# snc98_3x4_Switch-block.net
KiCad netlist of a schematic drawn in EAGLE
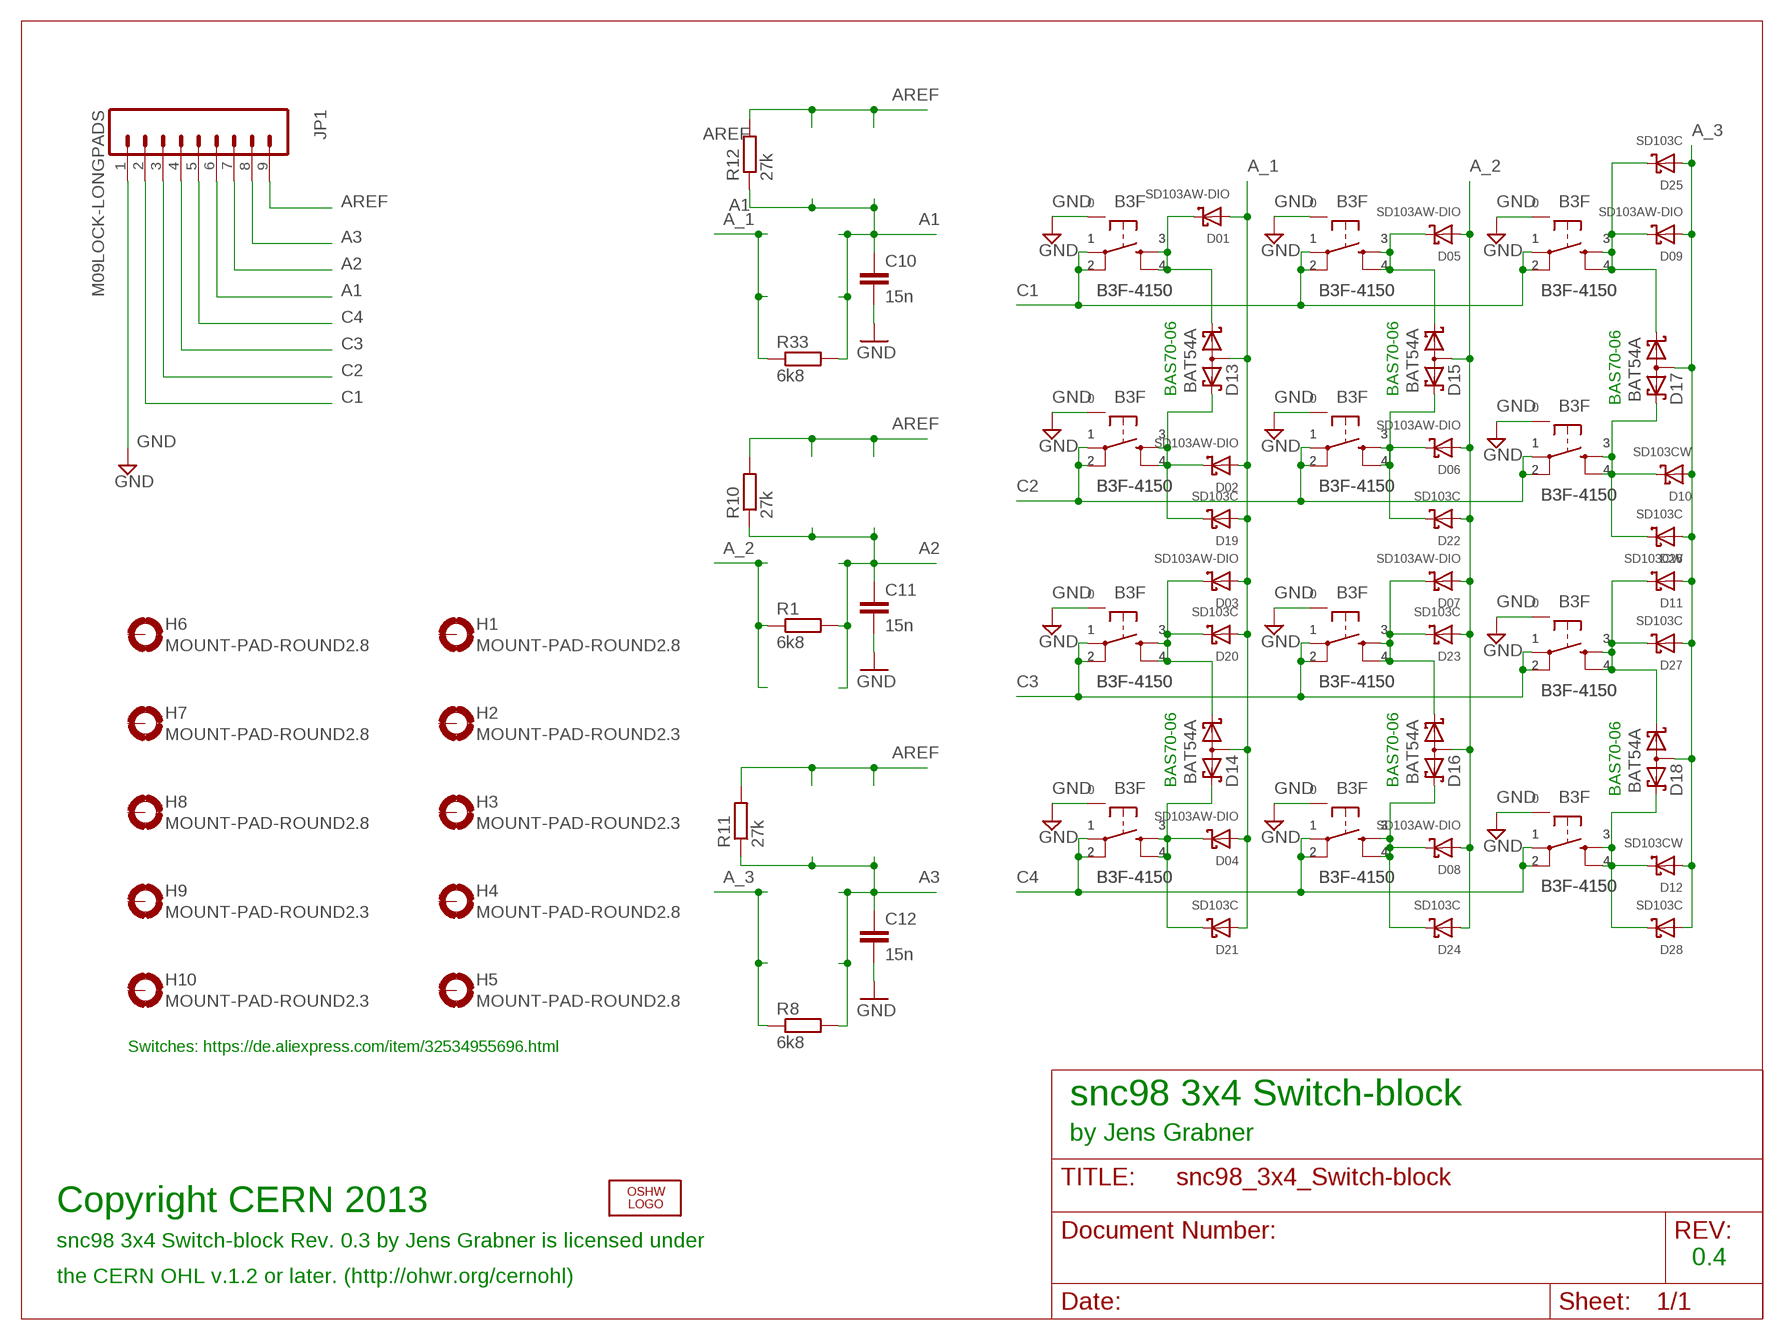
[diagram p0: schematic, sheet 1]

(export (version "E")
  (design (tool "Eeschema 10.0.6"))
  (components
    (comp (ref "C10")
      (value "15n")
      (footprint "eagle-import:C1206K")
      (libsource (lib "eagle-import") (part "C-EUC1206K"))
    )
    (comp (ref "C11")
      (value "15n")
      (footprint "eagle-import:C1206K")
      (libsource (lib "eagle-import") (part "C-EUC1206K"))
    )
    (comp (ref "C12")
      (value "15n")
      (footprint "eagle-import:C1206K")
      (libsource (lib "eagle-import") (part "C-EUC1206K"))
    )
    (comp (ref "D01")
      (value "SD103AW-DIO")
      (footprint "eagle-import:SOD-123F")
      (fields (field (name "MF") "MULTICOMP") (field (name "MPN") "SD103CW-7-F"))
      (libsource (lib "eagle-import") (part "DIODESOD-123F"))
    )
    (comp (ref "D02")
      (value "SD103AW-DIO")
      (footprint "eagle-import:SOD-123F")
      (fields (field (name "MF") "MULTICOMP") (field (name "MPN") "SD103CW-7-F"))
      (libsource (lib "eagle-import") (part "DIODESOD-123F"))
    )
    (comp (ref "D03")
      (value "SD103AW-DIO")
      (footprint "eagle-import:SOD-123F")
      (fields (field (name "MF") "MULTICOMP") (field (name "MPN") "SD103CW-7-F"))
      (libsource (lib "eagle-import") (part "DIODESOD-123F"))
    )
    (comp (ref "D04")
      (value "SD103AW-DIO")
      (footprint "eagle-import:SOD-123F")
      (fields (field (name "MF") "MULTICOMP") (field (name "MPN") "SD103CW-7-F"))
      (libsource (lib "eagle-import") (part "DIODESOD-123F"))
    )
    (comp (ref "D05")
      (value "SD103AW-DIO")
      (footprint "eagle-import:SOD-123F")
      (fields (field (name "MF") "MULTICOMP") (field (name "MPN") "SD103CW-7-F"))
      (libsource (lib "eagle-import") (part "DIODESOD-123F"))
    )
    (comp (ref "D06")
      (value "SD103AW-DIO")
      (footprint "eagle-import:SOD-123F")
      (fields (field (name "MF") "MULTICOMP") (field (name "MPN") "SD103CW-7-F"))
      (libsource (lib "eagle-import") (part "DIODESOD-123F"))
    )
    (comp (ref "D07")
      (value "SD103AW-DIO")
      (footprint "eagle-import:SOD-123F")
      (fields (field (name "MF") "MULTICOMP") (field (name "MPN") "SD103CW-7-F"))
      (libsource (lib "eagle-import") (part "DIODESOD-123F"))
    )
    (comp (ref "D08")
      (value "SD103AW-DIO")
      (footprint "eagle-import:SOD-123F")
      (fields (field (name "MF") "MULTICOMP") (field (name "MPN") "SD103CW-7-F"))
      (libsource (lib "eagle-import") (part "DIODESOD-123F"))
    )
    (comp (ref "D09")
      (value "SD103AW-DIO")
      (footprint "eagle-import:SOD-123F")
      (fields (field (name "MF") "MULTICOMP") (field (name "MPN") "SD103CW-7-F"))
      (libsource (lib "eagle-import") (part "DIODESOD-123F"))
    )
    (comp (ref "D10")
      (value "SD103CW")
      (footprint "eagle-import:SOD-123F")
      (fields (field (name "MF") "MULTICOMP") (field (name "MPN") "SD103CW-7-F"))
      (libsource (lib "eagle-import") (part "DIODESOD-123F"))
    )
    (comp (ref "D11")
      (value "SD103CW")
      (footprint "eagle-import:SOD-123F")
      (fields (field (name "MF") "MULTICOMP") (field (name "MPN") "SD103CW-7-F"))
      (libsource (lib "eagle-import") (part "DIODESOD-123F"))
    )
    (comp (ref "D12")
      (value "SD103CW")
      (footprint "eagle-import:SOD-123F")
      (fields (field (name "MF") "MULTICOMP") (field (name "MPN") "SD103CW-7-F"))
      (libsource (lib "eagle-import") (part "DIODESOD-123F"))
    )
    (comp (ref "D13")
      (value "BAT54A")
      (footprint "eagle-import:SOT23")
      (libsource (lib "eagle-import") (part "BAT54A"))
    )
    (comp (ref "D14")
      (value "BAT54A")
      (footprint "eagle-import:SOT23")
      (libsource (lib "eagle-import") (part "BAT54A"))
    )
    (comp (ref "D15")
      (value "BAT54A")
      (footprint "eagle-import:SOT23")
      (libsource (lib "eagle-import") (part "BAT54A"))
    )
    (comp (ref "D16")
      (value "BAT54A")
      (footprint "eagle-import:SOT23")
      (libsource (lib "eagle-import") (part "BAT54A"))
    )
    (comp (ref "D17")
      (value "BAT54A")
      (footprint "eagle-import:SOT23")
      (libsource (lib "eagle-import") (part "BAT54A"))
    )
    (comp (ref "D18")
      (value "BAT54A")
      (footprint "eagle-import:SOT23")
      (libsource (lib "eagle-import") (part "BAT54A"))
    )
    (comp (ref "D19")
      (value "SD103C")
      (footprint "eagle-import:280MIL-TH")
      (fields (field (name "MF") "MULTICOMP") (field (name "MPN") "SD103CW-7-F"))
      (libsource (lib "eagle-import") (part "DIODE280MIL-TH"))
    )
    (comp (ref "D20")
      (value "SD103C")
      (footprint "eagle-import:280MIL-TH")
      (fields (field (name "MF") "MULTICOMP") (field (name "MPN") "SD103CW-7-F"))
      (libsource (lib "eagle-import") (part "DIODE280MIL-TH"))
    )
    (comp (ref "D21")
      (value "SD103C")
      (footprint "eagle-import:280MIL-TH")
      (fields (field (name "MF") "MULTICOMP") (field (name "MPN") "SD103CW-7-F"))
      (libsource (lib "eagle-import") (part "DIODE280MIL-TH"))
    )
    (comp (ref "D22")
      (value "SD103C")
      (footprint "eagle-import:280MIL-TH")
      (fields (field (name "MF") "MULTICOMP") (field (name "MPN") "SD103CW-7-F"))
      (libsource (lib "eagle-import") (part "DIODE280MIL-TH"))
    )
    (comp (ref "D23")
      (value "SD103C")
      (footprint "eagle-import:280MIL-TH")
      (fields (field (name "MF") "MULTICOMP") (field (name "MPN") "SD103CW-7-F"))
      (libsource (lib "eagle-import") (part "DIODE280MIL-TH"))
    )
    (comp (ref "D24")
      (value "SD103C")
      (footprint "eagle-import:280MIL-TH")
      (fields (field (name "MF") "MULTICOMP") (field (name "MPN") "SD103CW-7-F"))
      (libsource (lib "eagle-import") (part "DIODE280MIL-TH"))
    )
    (comp (ref "D25")
      (value "SD103C")
      (footprint "eagle-import:280MIL-TH")
      (fields (field (name "MF") "MULTICOMP") (field (name "MPN") "SD103CW-7-F"))
      (libsource (lib "eagle-import") (part "DIODE280MIL-TH"))
    )
    (comp (ref "D26")
      (value "SD103C")
      (footprint "eagle-import:280MIL-TH")
      (fields (field (name "MF") "MULTICOMP") (field (name "MPN") "SD103CW-7-F"))
      (libsource (lib "eagle-import") (part "DIODE280MIL-TH"))
    )
    (comp (ref "D27")
      (value "SD103C")
      (footprint "eagle-import:280MIL-TH")
      (fields (field (name "MF") "MULTICOMP") (field (name "MPN") "SD103CW-7-F"))
      (libsource (lib "eagle-import") (part "DIODE280MIL-TH"))
    )
    (comp (ref "D28")
      (value "SD103C")
      (footprint "eagle-import:280MIL-TH")
      (fields (field (name "MF") "MULTICOMP") (field (name "MPN") "SD103CW-7-F"))
      (libsource (lib "eagle-import") (part "DIODE280MIL-TH"))
    )
    (comp (ref "H1")
      (value "MOUNT-PAD-ROUND2.8")
      (footprint "eagle-import:2,8-PAD")
      (libsource (lib "eagle-import") (part "MOUNT-PAD-ROUND2.8"))
    )
    (comp (ref "H2")
      (value "MOUNT-PAD-ROUND2.3")
      (footprint "eagle-import:2,3-PAD")
      (libsource (lib "eagle-import") (part "MOUNT-PAD-ROUND2.3"))
    )
    (comp (ref "H3")
      (value "MOUNT-PAD-ROUND2.3")
      (footprint "eagle-import:2,3-PAD")
      (libsource (lib "eagle-import") (part "MOUNT-PAD-ROUND2.3"))
    )
    (comp (ref "H4")
      (value "MOUNT-PAD-ROUND2.8")
      (footprint "eagle-import:2,8-PAD")
      (libsource (lib "eagle-import") (part "MOUNT-PAD-ROUND2.8"))
    )
    (comp (ref "H5")
      (value "MOUNT-PAD-ROUND2.8")
      (footprint "eagle-import:2,8-PAD")
      (libsource (lib "eagle-import") (part "MOUNT-PAD-ROUND2.8"))
    )
    (comp (ref "H6")
      (value "MOUNT-PAD-ROUND2.8")
      (footprint "eagle-import:2,8-PAD")
      (libsource (lib "eagle-import") (part "MOUNT-PAD-ROUND2.8"))
    )
    (comp (ref "H7")
      (value "MOUNT-PAD-ROUND2.8")
      (footprint "eagle-import:2,8-PAD")
      (libsource (lib "eagle-import") (part "MOUNT-PAD-ROUND2.8"))
    )
    (comp (ref "H8")
      (value "MOUNT-PAD-ROUND2.8")
      (footprint "eagle-import:2,8-PAD")
      (libsource (lib "eagle-import") (part "MOUNT-PAD-ROUND2.8"))
    )
    (comp (ref "H9")
      (value "MOUNT-PAD-ROUND2.3")
      (footprint "eagle-import:2,3-PAD")
      (libsource (lib "eagle-import") (part "MOUNT-PAD-ROUND2.3"))
    )
    (comp (ref "H10")
      (value "MOUNT-PAD-ROUND2.3")
      (footprint "eagle-import:2,3-PAD")
      (libsource (lib "eagle-import") (part "MOUNT-PAD-ROUND2.3"))
    )
    (comp (ref "JP1")
      (value "M09LOCK-LONGPADS")
      (footprint "eagle-import:1X09_LOCK_LONGPADS")
      (libsource (lib "eagle-import") (part "M09LOCK-LONGPADS"))
    )
    (comp (ref "LOGO1")
      (value "OSHW_LOGO_8MILX0150-NT")
      (footprint "eagle-import:OSHW_8X150_NOTEXT")
      (libsource (lib "eagle-import") (part "OSHW_LOGO_8MILX0150-NT"))
    )
    (comp (ref "R1")
      (value "6k8")
      (footprint "eagle-import:M0805")
      (libsource (lib "eagle-import") (part "R-EU_M0805"))
    )
    (comp (ref "R8")
      (value "6k8")
      (footprint "eagle-import:M0805")
      (libsource (lib "eagle-import") (part "R-EU_M0805"))
    )
    (comp (ref "R10")
      (value "27k")
      (footprint "eagle-import:M0805")
      (libsource (lib "eagle-import") (part "R-EU_M0805"))
    )
    (comp (ref "R11")
      (value "27k")
      (footprint "eagle-import:M0805")
      (libsource (lib "eagle-import") (part "R-EU_M0805"))
    )
    (comp (ref "R12")
      (value "27k")
      (footprint "eagle-import:M0805")
      (libsource (lib "eagle-import") (part "R-EU_M0805"))
    )
    (comp (ref "R33")
      (value "6k8")
      (footprint "eagle-import:M0805")
      (libsource (lib "eagle-import") (part "R-EU_M0805"))
    )
    (comp (ref "S1")
      (value "B3F-4150")
      (footprint "eagle-import:TACTILE-PTH-12MM")
      (libsource (lib "eagle-import") (part "TACTILE_SWITCHTACTILE_SWITCH_PTH-12MM"))
    )
    (comp (ref "S2")
      (value "B3F-4150")
      (footprint "eagle-import:TACTILE-PTH-12MM")
      (libsource (lib "eagle-import") (part "TACTILE_SWITCHTACTILE_SWITCH_PTH-12MM"))
    )
    (comp (ref "S3")
      (value "B3F-4150")
      (footprint "eagle-import:TACTILE-PTH-12MM")
      (libsource (lib "eagle-import") (part "TACTILE_SWITCHTACTILE_SWITCH_PTH-12MM"))
    )
    (comp (ref "S4")
      (value "B3F-4150")
      (footprint "eagle-import:TACTILE-PTH-12MM")
      (libsource (lib "eagle-import") (part "TACTILE_SWITCHTACTILE_SWITCH_PTH-12MM"))
    )
    (comp (ref "S5")
      (value "B3F-4150")
      (footprint "eagle-import:TACTILE-PTH-12MM")
      (libsource (lib "eagle-import") (part "TACTILE_SWITCHTACTILE_SWITCH_PTH-12MM"))
    )
    (comp (ref "S6")
      (value "B3F-4150")
      (footprint "eagle-import:TACTILE-PTH-12MM")
      (libsource (lib "eagle-import") (part "TACTILE_SWITCHTACTILE_SWITCH_PTH-12MM"))
    )
    (comp (ref "S7")
      (value "B3F-4150")
      (footprint "eagle-import:TACTILE-PTH-12MM")
      (libsource (lib "eagle-import") (part "TACTILE_SWITCHTACTILE_SWITCH_PTH-12MM"))
    )
    (comp (ref "S8")
      (value "B3F-4150")
      (footprint "eagle-import:TACTILE-PTH-12MM")
      (libsource (lib "eagle-import") (part "TACTILE_SWITCHTACTILE_SWITCH_PTH-12MM"))
    )
    (comp (ref "S9")
      (value "B3F-4150")
      (footprint "eagle-import:TACTILE-PTH-12MM")
      (libsource (lib "eagle-import") (part "TACTILE_SWITCHTACTILE_SWITCH_PTH-12MM"))
    )
    (comp (ref "S10")
      (value "B3F-4150")
      (footprint "eagle-import:TACTILE-PTH-12MM")
      (libsource (lib "eagle-import") (part "TACTILE_SWITCHTACTILE_SWITCH_PTH-12MM"))
    )
    (comp (ref "S11")
      (value "B3F-4150")
      (footprint "eagle-import:TACTILE-PTH-12MM")
      (libsource (lib "eagle-import") (part "TACTILE_SWITCHTACTILE_SWITCH_PTH-12MM"))
    )
    (comp (ref "S12")
      (value "B3F-4150")
      (footprint "eagle-import:TACTILE-PTH-12MM")
      (libsource (lib "eagle-import") (part "TACTILE_SWITCHTACTILE_SWITCH_PTH-12MM"))
    )
  )
  (nets
    (net (code "1") (name "/A1") (class "Default")
      (node (ref "C10") (pin "1") (pinfunction "1_1") (pintype "passive"))
      (node (ref "JP1") (pin "6") (pinfunction "6_6") (pintype "passive"))
      (node (ref "R12") (pin "1") (pinfunction "1_1") (pintype "passive"))
      (node (ref "R33") (pin "2") (pinfunction "2_2") (pintype "passive"))
    )
    (net (code "2") (name "/A2") (class "Default")
      (node (ref "C11") (pin "1") (pinfunction "1_1") (pintype "passive"))
      (node (ref "JP1") (pin "7") (pinfunction "7_7") (pintype "passive"))
      (node (ref "R1") (pin "2") (pinfunction "2_2") (pintype "passive"))
      (node (ref "R10") (pin "1") (pinfunction "1_1") (pintype "passive"))
    )
    (net (code "3") (name "/A3") (class "Default")
      (node (ref "C12") (pin "1") (pinfunction "1_1") (pintype "passive"))
      (node (ref "JP1") (pin "8") (pinfunction "8_8") (pintype "passive"))
      (node (ref "R11") (pin "1") (pinfunction "1_1") (pintype "passive"))
      (node (ref "R8") (pin "2") (pinfunction "2_2") (pintype "passive"))
    )
    (net (code "4") (name "/AREF") (class "Default")
      (node (ref "JP1") (pin "9") (pinfunction "9_9") (pintype "passive"))
      (node (ref "R10") (pin "2") (pinfunction "2_2") (pintype "passive"))
      (node (ref "R11") (pin "2") (pinfunction "2_2") (pintype "passive"))
      (node (ref "R12") (pin "2") (pinfunction "2_2") (pintype "passive"))
    )
    (net (code "5") (name "/A_1") (class "Default")
      (node (ref "D01") (pin "A") (pinfunction "A_A") (pintype "passive"))
      (node (ref "D02") (pin "A") (pinfunction "A_A") (pintype "passive"))
      (node (ref "D03") (pin "A") (pinfunction "A_A") (pintype "passive"))
      (node (ref "D04") (pin "A") (pinfunction "A_A") (pintype "passive"))
      (node (ref "D13") (pin "3") (pinfunction "AA_3") (pintype "passive"))
      (node (ref "D14") (pin "3") (pinfunction "AA_3") (pintype "passive"))
      (node (ref "D19") (pin "P$1") (pinfunction "A_P$1") (pintype "passive"))
      (node (ref "D20") (pin "P$1") (pinfunction "A_P$1") (pintype "passive"))
      (node (ref "D21") (pin "P$1") (pinfunction "A_P$1") (pintype "passive"))
      (node (ref "R33") (pin "1") (pinfunction "1_1") (pintype "passive"))
    )
    (net (code "6") (name "/A_2") (class "Default")
      (node (ref "D05") (pin "A") (pinfunction "A_A") (pintype "passive"))
      (node (ref "D06") (pin "A") (pinfunction "A_A") (pintype "passive"))
      (node (ref "D07") (pin "A") (pinfunction "A_A") (pintype "passive"))
      (node (ref "D08") (pin "A") (pinfunction "A_A") (pintype "passive"))
      (node (ref "D15") (pin "3") (pinfunction "AA_3") (pintype "passive"))
      (node (ref "D16") (pin "3") (pinfunction "AA_3") (pintype "passive"))
      (node (ref "D22") (pin "P$1") (pinfunction "A_P$1") (pintype "passive"))
      (node (ref "D23") (pin "P$1") (pinfunction "A_P$1") (pintype "passive"))
      (node (ref "D24") (pin "P$1") (pinfunction "A_P$1") (pintype "passive"))
      (node (ref "R1") (pin "1") (pinfunction "1_1") (pintype "passive"))
    )
    (net (code "7") (name "/A_3") (class "Default")
      (node (ref "D09") (pin "A") (pinfunction "A_A") (pintype "passive"))
      (node (ref "D10") (pin "A") (pinfunction "A_A") (pintype "passive"))
      (node (ref "D11") (pin "A") (pinfunction "A_A") (pintype "passive"))
      (node (ref "D12") (pin "A") (pinfunction "A_A") (pintype "passive"))
      (node (ref "D17") (pin "3") (pinfunction "AA_3") (pintype "passive"))
      (node (ref "D18") (pin "3") (pinfunction "AA_3") (pintype "passive"))
      (node (ref "D25") (pin "P$1") (pinfunction "A_P$1") (pintype "passive"))
      (node (ref "D26") (pin "P$1") (pinfunction "A_P$1") (pintype "passive"))
      (node (ref "D27") (pin "P$1") (pinfunction "A_P$1") (pintype "passive"))
      (node (ref "D28") (pin "P$1") (pinfunction "A_P$1") (pintype "passive"))
      (node (ref "R8") (pin "1") (pinfunction "1_1") (pintype "passive"))
    )
    (net (code "8") (name "/C1") (class "Default")
      (node (ref "JP1") (pin "2") (pinfunction "2_2") (pintype "passive"))
      (node (ref "S1") (pin "P$1") (pinfunction "1_P$1") (pintype "passive"))
      (node (ref "S1") (pin "P$11") (pinfunction "1_P$11") (pintype "passive"))
      (node (ref "S1") (pin "P$12") (pinfunction "2_P$12") (pintype "passive"))
      (node (ref "S1") (pin "P$2") (pinfunction "2_P$2") (pintype "passive"))
      (node (ref "S1") (pin "P$21") (pinfunction "1_P$21") (pintype "passive"))
      (node (ref "S1") (pin "P$22") (pinfunction "2_P$22") (pintype "passive"))
      (node (ref "S5") (pin "P$1") (pinfunction "1_P$1") (pintype "passive"))
      (node (ref "S5") (pin "P$11") (pinfunction "1_P$11") (pintype "passive"))
      (node (ref "S5") (pin "P$12") (pinfunction "2_P$12") (pintype "passive"))
      (node (ref "S5") (pin "P$2") (pinfunction "2_P$2") (pintype "passive"))
      (node (ref "S5") (pin "P$21") (pinfunction "1_P$21") (pintype "passive"))
      (node (ref "S5") (pin "P$22") (pinfunction "2_P$22") (pintype "passive"))
      (node (ref "S9") (pin "P$1") (pinfunction "1_P$1") (pintype "passive"))
      (node (ref "S9") (pin "P$11") (pinfunction "1_P$11") (pintype "passive"))
      (node (ref "S9") (pin "P$12") (pinfunction "2_P$12") (pintype "passive"))
      (node (ref "S9") (pin "P$2") (pinfunction "2_P$2") (pintype "passive"))
      (node (ref "S9") (pin "P$21") (pinfunction "1_P$21") (pintype "passive"))
      (node (ref "S9") (pin "P$22") (pinfunction "2_P$22") (pintype "passive"))
    )
    (net (code "9") (name "/C2") (class "Default")
      (node (ref "JP1") (pin "3") (pinfunction "3_3") (pintype "passive"))
      (node (ref "S10") (pin "P$1") (pinfunction "1_P$1") (pintype "passive"))
      (node (ref "S10") (pin "P$11") (pinfunction "1_P$11") (pintype "passive"))
      (node (ref "S10") (pin "P$12") (pinfunction "2_P$12") (pintype "passive"))
      (node (ref "S10") (pin "P$2") (pinfunction "2_P$2") (pintype "passive"))
      (node (ref "S10") (pin "P$21") (pinfunction "1_P$21") (pintype "passive"))
      (node (ref "S10") (pin "P$22") (pinfunction "2_P$22") (pintype "passive"))
      (node (ref "S2") (pin "P$1") (pinfunction "1_P$1") (pintype "passive"))
      (node (ref "S2") (pin "P$11") (pinfunction "1_P$11") (pintype "passive"))
      (node (ref "S2") (pin "P$12") (pinfunction "2_P$12") (pintype "passive"))
      (node (ref "S2") (pin "P$2") (pinfunction "2_P$2") (pintype "passive"))
      (node (ref "S2") (pin "P$21") (pinfunction "1_P$21") (pintype "passive"))
      (node (ref "S2") (pin "P$22") (pinfunction "2_P$22") (pintype "passive"))
      (node (ref "S6") (pin "P$1") (pinfunction "1_P$1") (pintype "passive"))
      (node (ref "S6") (pin "P$11") (pinfunction "1_P$11") (pintype "passive"))
      (node (ref "S6") (pin "P$12") (pinfunction "2_P$12") (pintype "passive"))
      (node (ref "S6") (pin "P$2") (pinfunction "2_P$2") (pintype "passive"))
      (node (ref "S6") (pin "P$21") (pinfunction "1_P$21") (pintype "passive"))
      (node (ref "S6") (pin "P$22") (pinfunction "2_P$22") (pintype "passive"))
    )
    (net (code "10") (name "/C3") (class "Default")
      (node (ref "JP1") (pin "4") (pinfunction "4_4") (pintype "passive"))
      (node (ref "S11") (pin "P$1") (pinfunction "1_P$1") (pintype "passive"))
      (node (ref "S11") (pin "P$11") (pinfunction "1_P$11") (pintype "passive"))
      (node (ref "S11") (pin "P$12") (pinfunction "2_P$12") (pintype "passive"))
      (node (ref "S11") (pin "P$2") (pinfunction "2_P$2") (pintype "passive"))
      (node (ref "S11") (pin "P$21") (pinfunction "1_P$21") (pintype "passive"))
      (node (ref "S11") (pin "P$22") (pinfunction "2_P$22") (pintype "passive"))
      (node (ref "S3") (pin "P$1") (pinfunction "1_P$1") (pintype "passive"))
      (node (ref "S3") (pin "P$11") (pinfunction "1_P$11") (pintype "passive"))
      (node (ref "S3") (pin "P$12") (pinfunction "2_P$12") (pintype "passive"))
      (node (ref "S3") (pin "P$2") (pinfunction "2_P$2") (pintype "passive"))
      (node (ref "S3") (pin "P$21") (pinfunction "1_P$21") (pintype "passive"))
      (node (ref "S3") (pin "P$22") (pinfunction "2_P$22") (pintype "passive"))
      (node (ref "S7") (pin "P$1") (pinfunction "1_P$1") (pintype "passive"))
      (node (ref "S7") (pin "P$11") (pinfunction "1_P$11") (pintype "passive"))
      (node (ref "S7") (pin "P$12") (pinfunction "2_P$12") (pintype "passive"))
      (node (ref "S7") (pin "P$2") (pinfunction "2_P$2") (pintype "passive"))
      (node (ref "S7") (pin "P$21") (pinfunction "1_P$21") (pintype "passive"))
      (node (ref "S7") (pin "P$22") (pinfunction "2_P$22") (pintype "passive"))
    )
    (net (code "11") (name "/C4") (class "Default")
      (node (ref "JP1") (pin "5") (pinfunction "5_5") (pintype "passive"))
      (node (ref "S12") (pin "P$1") (pinfunction "1_P$1") (pintype "passive"))
      (node (ref "S12") (pin "P$11") (pinfunction "1_P$11") (pintype "passive"))
      (node (ref "S12") (pin "P$12") (pinfunction "2_P$12") (pintype "passive"))
      (node (ref "S12") (pin "P$2") (pinfunction "2_P$2") (pintype "passive"))
      (node (ref "S12") (pin "P$21") (pinfunction "1_P$21") (pintype "passive"))
      (node (ref "S12") (pin "P$22") (pinfunction "2_P$22") (pintype "passive"))
      (node (ref "S4") (pin "P$1") (pinfunction "1_P$1") (pintype "passive"))
      (node (ref "S4") (pin "P$11") (pinfunction "1_P$11") (pintype "passive"))
      (node (ref "S4") (pin "P$12") (pinfunction "2_P$12") (pintype "passive"))
      (node (ref "S4") (pin "P$2") (pinfunction "2_P$2") (pintype "passive"))
      (node (ref "S4") (pin "P$21") (pinfunction "1_P$21") (pintype "passive"))
      (node (ref "S4") (pin "P$22") (pinfunction "2_P$22") (pintype "passive"))
      (node (ref "S8") (pin "P$1") (pinfunction "1_P$1") (pintype "passive"))
      (node (ref "S8") (pin "P$11") (pinfunction "1_P$11") (pintype "passive"))
      (node (ref "S8") (pin "P$12") (pinfunction "2_P$12") (pintype "passive"))
      (node (ref "S8") (pin "P$2") (pinfunction "2_P$2") (pintype "passive"))
      (node (ref "S8") (pin "P$21") (pinfunction "1_P$21") (pintype "passive"))
      (node (ref "S8") (pin "P$22") (pinfunction "2_P$22") (pintype "passive"))
    )
    (net (code "12") (name "GND") (class "Default")
      (node (ref "C10") (pin "2") (pinfunction "2_2") (pintype "passive"))
      (node (ref "C11") (pin "2") (pinfunction "2_2") (pintype "passive"))
      (node (ref "C12") (pin "2") (pinfunction "2_2") (pintype "passive"))
      (node (ref "JP1") (pin "1") (pinfunction "1_1") (pintype "passive"))
      (node (ref "S1") (pin "P$15") (pinfunction "5_P$15") (pintype "passive"))
      (node (ref "S10") (pin "P$15") (pinfunction "5_P$15") (pintype "passive"))
      (node (ref "S11") (pin "P$15") (pinfunction "5_P$15") (pintype "passive"))
      (node (ref "S12") (pin "P$15") (pinfunction "5_P$15") (pintype "passive"))
      (node (ref "S2") (pin "P$15") (pinfunction "5_P$15") (pintype "passive"))
      (node (ref "S3") (pin "P$15") (pinfunction "5_P$15") (pintype "passive"))
      (node (ref "S4") (pin "P$15") (pinfunction "5_P$15") (pintype "passive"))
      (node (ref "S5") (pin "P$15") (pinfunction "5_P$15") (pintype "passive"))
      (node (ref "S6") (pin "P$15") (pinfunction "5_P$15") (pintype "passive"))
      (node (ref "S7") (pin "P$15") (pinfunction "5_P$15") (pintype "passive"))
      (node (ref "S8") (pin "P$15") (pinfunction "5_P$15") (pintype "passive"))
      (node (ref "S9") (pin "P$15") (pinfunction "5_P$15") (pintype "passive"))
    )
    (net (code "13") (name "Net-(D13-K1)") (class "Default")
      (node (ref "D01") (pin "C") (pinfunction "C_C") (pintype "passive"))
      (node (ref "D13") (pin "1") (pinfunction "K1_1") (pintype "passive"))
      (node (ref "S1") (pin "P$13") (pinfunction "3_P$13") (pintype "passive"))
      (node (ref "S1") (pin "P$14") (pinfunction "4_P$14") (pintype "passive"))
      (node (ref "S1") (pin "P$23") (pinfunction "3_P$23") (pintype "passive"))
      (node (ref "S1") (pin "P$24") (pinfunction "4_P$24") (pintype "passive"))
      (node (ref "S1") (pin "P$3") (pinfunction "3_P$3") (pintype "passive"))
      (node (ref "S1") (pin "P$4") (pinfunction "4_P$4") (pintype "passive"))
    )
    (net (code "14") (name "Net-(D13-K2)") (class "Default")
      (node (ref "D02") (pin "C") (pinfunction "C_C") (pintype "passive"))
      (node (ref "D13") (pin "2") (pinfunction "K2_2") (pintype "passive"))
      (node (ref "D19") (pin "P$2") (pinfunction "C_P$2") (pintype "passive"))
      (node (ref "S2") (pin "P$13") (pinfunction "3_P$13") (pintype "passive"))
      (node (ref "S2") (pin "P$14") (pinfunction "4_P$14") (pintype "passive"))
      (node (ref "S2") (pin "P$23") (pinfunction "3_P$23") (pintype "passive"))
      (node (ref "S2") (pin "P$24") (pinfunction "4_P$24") (pintype "passive"))
      (node (ref "S2") (pin "P$3") (pinfunction "3_P$3") (pintype "passive"))
      (node (ref "S2") (pin "P$4") (pinfunction "4_P$4") (pintype "passive"))
    )
    (net (code "15") (name "Net-(D14-K1)") (class "Default")
      (node (ref "D03") (pin "C") (pinfunction "C_C") (pintype "passive"))
      (node (ref "D14") (pin "1") (pinfunction "K1_1") (pintype "passive"))
      (node (ref "D20") (pin "P$2") (pinfunction "C_P$2") (pintype "passive"))
      (node (ref "S3") (pin "P$13") (pinfunction "3_P$13") (pintype "passive"))
      (node (ref "S3") (pin "P$14") (pinfunction "4_P$14") (pintype "passive"))
      (node (ref "S3") (pin "P$23") (pinfunction "3_P$23") (pintype "passive"))
      (node (ref "S3") (pin "P$24") (pinfunction "4_P$24") (pintype "passive"))
      (node (ref "S3") (pin "P$3") (pinfunction "3_P$3") (pintype "passive"))
      (node (ref "S3") (pin "P$4") (pinfunction "4_P$4") (pintype "passive"))
    )
    (net (code "16") (name "Net-(D14-K2)") (class "Default")
      (node (ref "D04") (pin "C") (pinfunction "C_C") (pintype "passive"))
      (node (ref "D14") (pin "2") (pinfunction "K2_2") (pintype "passive"))
      (node (ref "D21") (pin "P$2") (pinfunction "C_P$2") (pintype "passive"))
      (node (ref "S4") (pin "P$13") (pinfunction "3_P$13") (pintype "passive"))
      (node (ref "S4") (pin "P$14") (pinfunction "4_P$14") (pintype "passive"))
      (node (ref "S4") (pin "P$23") (pinfunction "3_P$23") (pintype "passive"))
      (node (ref "S4") (pin "P$24") (pinfunction "4_P$24") (pintype "passive"))
      (node (ref "S4") (pin "P$3") (pinfunction "3_P$3") (pintype "passive"))
      (node (ref "S4") (pin "P$4") (pinfunction "4_P$4") (pintype "passive"))
    )
    (net (code "17") (name "Net-(D15-K1)") (class "Default")
      (node (ref "D05") (pin "C") (pinfunction "C_C") (pintype "passive"))
      (node (ref "D15") (pin "1") (pinfunction "K1_1") (pintype "passive"))
      (node (ref "S5") (pin "P$13") (pinfunction "3_P$13") (pintype "passive"))
      (node (ref "S5") (pin "P$14") (pinfunction "4_P$14") (pintype "passive"))
      (node (ref "S5") (pin "P$23") (pinfunction "3_P$23") (pintype "passive"))
      (node (ref "S5") (pin "P$24") (pinfunction "4_P$24") (pintype "passive"))
      (node (ref "S5") (pin "P$3") (pinfunction "3_P$3") (pintype "passive"))
      (node (ref "S5") (pin "P$4") (pinfunction "4_P$4") (pintype "passive"))
    )
    (net (code "18") (name "Net-(D15-K2)") (class "Default")
      (node (ref "D06") (pin "C") (pinfunction "C_C") (pintype "passive"))
      (node (ref "D15") (pin "2") (pinfunction "K2_2") (pintype "passive"))
      (node (ref "D22") (pin "P$2") (pinfunction "C_P$2") (pintype "passive"))
      (node (ref "S6") (pin "P$13") (pinfunction "3_P$13") (pintype "passive"))
      (node (ref "S6") (pin "P$14") (pinfunction "4_P$14") (pintype "passive"))
      (node (ref "S6") (pin "P$23") (pinfunction "3_P$23") (pintype "passive"))
      (node (ref "S6") (pin "P$24") (pinfunction "4_P$24") (pintype "passive"))
      (node (ref "S6") (pin "P$3") (pinfunction "3_P$3") (pintype "passive"))
      (node (ref "S6") (pin "P$4") (pinfunction "4_P$4") (pintype "passive"))
    )
    (net (code "19") (name "Net-(D16-K1)") (class "Default")
      (node (ref "D07") (pin "C") (pinfunction "C_C") (pintype "passive"))
      (node (ref "D16") (pin "1") (pinfunction "K1_1") (pintype "passive"))
      (node (ref "D23") (pin "P$2") (pinfunction "C_P$2") (pintype "passive"))
      (node (ref "S7") (pin "P$13") (pinfunction "3_P$13") (pintype "passive"))
      (node (ref "S7") (pin "P$14") (pinfunction "4_P$14") (pintype "passive"))
      (node (ref "S7") (pin "P$23") (pinfunction "3_P$23") (pintype "passive"))
      (node (ref "S7") (pin "P$24") (pinfunction "4_P$24") (pintype "passive"))
      (node (ref "S7") (pin "P$3") (pinfunction "3_P$3") (pintype "passive"))
      (node (ref "S7") (pin "P$4") (pinfunction "4_P$4") (pintype "passive"))
    )
    (net (code "20") (name "Net-(D16-K2)") (class "Default")
      (node (ref "D08") (pin "C") (pinfunction "C_C") (pintype "passive"))
      (node (ref "D16") (pin "2") (pinfunction "K2_2") (pintype "passive"))
      (node (ref "D24") (pin "P$2") (pinfunction "C_P$2") (pintype "passive"))
      (node (ref "S8") (pin "P$13") (pinfunction "3_P$13") (pintype "passive"))
      (node (ref "S8") (pin "P$14") (pinfunction "4_P$14") (pintype "passive"))
      (node (ref "S8") (pin "P$23") (pinfunction "3_P$23") (pintype "passive"))
      (node (ref "S8") (pin "P$24") (pinfunction "4_P$24") (pintype "passive"))
      (node (ref "S8") (pin "P$3") (pinfunction "3_P$3") (pintype "passive"))
      (node (ref "S8") (pin "P$4") (pinfunction "4_P$4") (pintype "passive"))
    )
    (net (code "21") (name "Net-(D17-K1)") (class "Default")
      (node (ref "D09") (pin "C") (pinfunction "C_C") (pintype "passive"))
      (node (ref "D17") (pin "1") (pinfunction "K1_1") (pintype "passive"))
      (node (ref "D25") (pin "P$2") (pinfunction "C_P$2") (pintype "passive"))
      (node (ref "S9") (pin "P$13") (pinfunction "3_P$13") (pintype "passive"))
      (node (ref "S9") (pin "P$14") (pinfunction "4_P$14") (pintype "passive"))
      (node (ref "S9") (pin "P$23") (pinfunction "3_P$23") (pintype "passive"))
      (node (ref "S9") (pin "P$24") (pinfunction "4_P$24") (pintype "passive"))
      (node (ref "S9") (pin "P$3") (pinfunction "3_P$3") (pintype "passive"))
      (node (ref "S9") (pin "P$4") (pinfunction "4_P$4") (pintype "passive"))
    )
    (net (code "22") (name "Net-(D17-K2)") (class "Default")
      (node (ref "D10") (pin "C") (pinfunction "C_C") (pintype "passive"))
      (node (ref "D17") (pin "2") (pinfunction "K2_2") (pintype "passive"))
      (node (ref "D26") (pin "P$2") (pinfunction "C_P$2") (pintype "passive"))
      (node (ref "S10") (pin "P$13") (pinfunction "3_P$13") (pintype "passive"))
      (node (ref "S10") (pin "P$14") (pinfunction "4_P$14") (pintype "passive"))
      (node (ref "S10") (pin "P$23") (pinfunction "3_P$23") (pintype "passive"))
      (node (ref "S10") (pin "P$24") (pinfunction "4_P$24") (pintype "passive"))
      (node (ref "S10") (pin "P$3") (pinfunction "3_P$3") (pintype "passive"))
      (node (ref "S10") (pin "P$4") (pinfunction "4_P$4") (pintype "passive"))
    )
    (net (code "23") (name "Net-(D18-K1)") (class "Default")
      (node (ref "D11") (pin "C") (pinfunction "C_C") (pintype "passive"))
      (node (ref "D18") (pin "1") (pinfunction "K1_1") (pintype "passive"))
      (node (ref "D27") (pin "P$2") (pinfunction "C_P$2") (pintype "passive"))
      (node (ref "S11") (pin "P$13") (pinfunction "3_P$13") (pintype "passive"))
      (node (ref "S11") (pin "P$14") (pinfunction "4_P$14") (pintype "passive"))
      (node (ref "S11") (pin "P$23") (pinfunction "3_P$23") (pintype "passive"))
      (node (ref "S11") (pin "P$24") (pinfunction "4_P$24") (pintype "passive"))
      (node (ref "S11") (pin "P$3") (pinfunction "3_P$3") (pintype "passive"))
      (node (ref "S11") (pin "P$4") (pinfunction "4_P$4") (pintype "passive"))
    )
    (net (code "24") (name "Net-(D18-K2)") (class "Default")
      (node (ref "D12") (pin "C") (pinfunction "C_C") (pintype "passive"))
      (node (ref "D18") (pin "2") (pinfunction "K2_2") (pintype "passive"))
      (node (ref "D28") (pin "P$2") (pinfunction "C_P$2") (pintype "passive"))
      (node (ref "S12") (pin "P$13") (pinfunction "3_P$13") (pintype "passive"))
      (node (ref "S12") (pin "P$14") (pinfunction "4_P$14") (pintype "passive"))
      (node (ref "S12") (pin "P$23") (pinfunction "3_P$23") (pintype "passive"))
      (node (ref "S12") (pin "P$24") (pinfunction "4_P$24") (pintype "passive"))
      (node (ref "S12") (pin "P$3") (pinfunction "3_P$3") (pintype "passive"))
      (node (ref "S12") (pin "P$4") (pinfunction "4_P$4") (pintype "passive"))
    )
    (net (code "25") (name "unconnected-(H1-MOUNT-PadB2,8)") (class "Default")
      (node (ref "H1") (pin "B2,8") (pinfunction "MOUNT_B2,8") (pintype "passive"))
    )
    (net (code "26") (name "unconnected-(H2-MOUNT-PadB2,8)") (class "Default")
      (node (ref "H2") (pin "B2,8") (pinfunction "MOUNT_B2,8") (pintype "passive"))
    )
    (net (code "27") (name "unconnected-(H3-MOUNT-PadB2,8)") (class "Default")
      (node (ref "H3") (pin "B2,8") (pinfunction "MOUNT_B2,8") (pintype "passive"))
    )
    (net (code "28") (name "unconnected-(H4-MOUNT-PadB2,8)") (class "Default")
      (node (ref "H4") (pin "B2,8") (pinfunction "MOUNT_B2,8") (pintype "passive"))
    )
    (net (code "29") (name "unconnected-(H5-MOUNT-PadB2,8)") (class "Default")
      (node (ref "H5") (pin "B2,8") (pinfunction "MOUNT_B2,8") (pintype "passive"))
    )
    (net (code "30") (name "unconnected-(H6-MOUNT-PadB2,8)") (class "Default")
      (node (ref "H6") (pin "B2,8") (pinfunction "MOUNT_B2,8") (pintype "passive"))
    )
    (net (code "31") (name "unconnected-(H7-MOUNT-PadB2,8)") (class "Default")
      (node (ref "H7") (pin "B2,8") (pinfunction "MOUNT_B2,8") (pintype "passive"))
    )
    (net (code "32") (name "unconnected-(H8-MOUNT-PadB2,8)") (class "Default")
      (node (ref "H8") (pin "B2,8") (pinfunction "MOUNT_B2,8") (pintype "passive"))
    )
    (net (code "33") (name "unconnected-(H9-MOUNT-PadB2,8)") (class "Default")
      (node (ref "H9") (pin "B2,8") (pinfunction "MOUNT_B2,8") (pintype "passive"))
    )
    (net (code "34") (name "unconnected-(H10-MOUNT-PadB2,8)") (class "Default")
      (node (ref "H10") (pin "B2,8") (pinfunction "MOUNT_B2,8") (pintype "passive"))
    )
  )
)
